# Rev_A.net
KiCad netlist of a schematic drawn in EAGLE
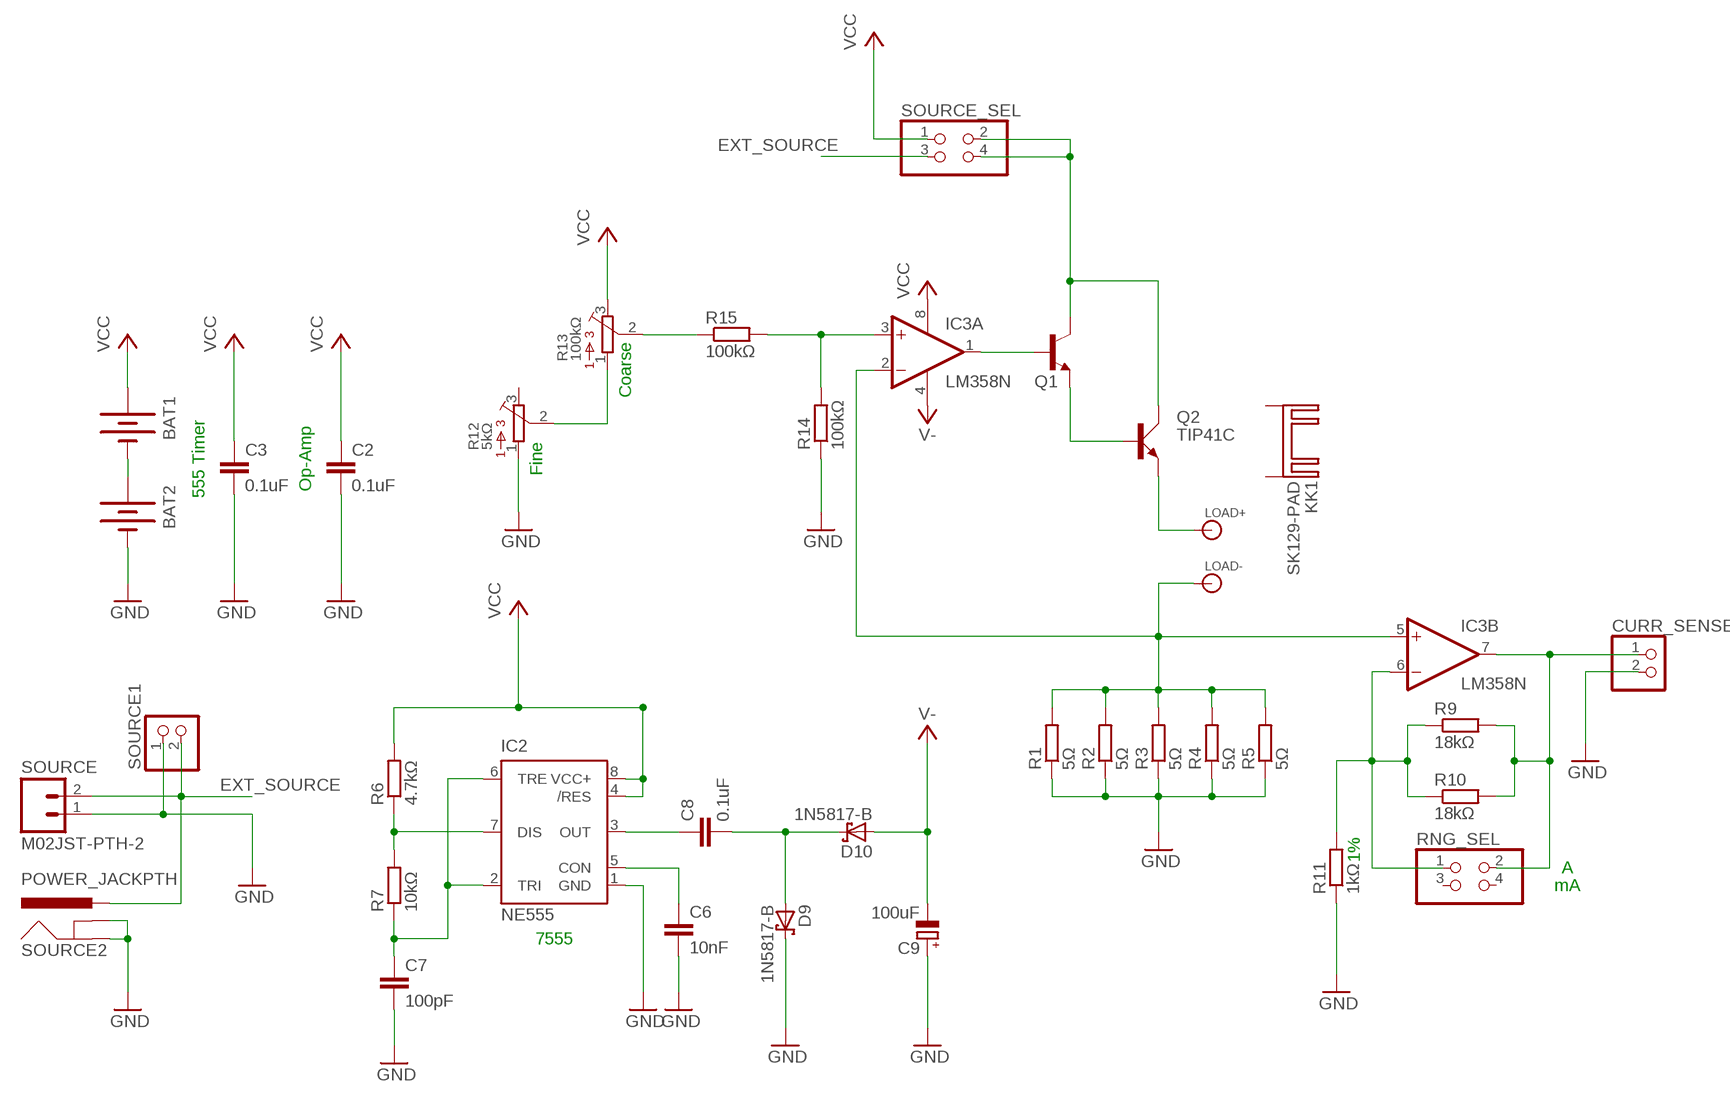
[diagram p0: schematic, sheet 1]

(export (version "E")
  (design (tool "Eeschema 10.0.6"))
  (components
    (comp (ref "BAT1")
      (value "BATTERYAA")
      (footprint "eagle-import:BATTERY-AA")
      (libsource (lib "eagle-import") (part "BATTERYAA"))
    )
    (comp (ref "BAT2")
      (value "BATTERYAA")
      (footprint "eagle-import:BATTERY-AA")
      (libsource (lib "eagle-import") (part "BATTERYAA"))
    )
    (comp (ref "C2")
      (value "0.1uF")
      (footprint "eagle-import:C050-025X075")
      (libsource (lib "eagle-import") (part "C-EU050-025X075"))
    )
    (comp (ref "C3")
      (value "0.1uF")
      (footprint "eagle-import:C050-025X075")
      (libsource (lib "eagle-import") (part "C-EU050-025X075"))
    )
    (comp (ref "C6")
      (value "10nF")
      (footprint "eagle-import:C050-025X075")
      (libsource (lib "eagle-import") (part "C-EU050-025X075"))
    )
    (comp (ref "C7")
      (value "100pF")
      (footprint "eagle-import:C025-025X050")
      (libsource (lib "eagle-import") (part "C-EU025-025X050"))
    )
    (comp (ref "C8")
      (value "0.1uF")
      (footprint "eagle-import:C050-025X075")
      (libsource (lib "eagle-import") (part "C-EU050-025X075"))
    )
    (comp (ref "C9")
      (value "100uF")
      (footprint "eagle-import:E2,5-6")
      (libsource (lib "eagle-import") (part "CPOL-EUE2.5-6"))
    )
    (comp (ref "CURR_SENSE")
      (value "PINHD-1X2")
      (footprint "eagle-import:1X02")
      (libsource (lib "eagle-import") (part "PINHD-1X2"))
    )
    (comp (ref "D9")
      (value "1N5817-B")
      (footprint "eagle-import:DO41-7.6")
      (libsource (lib "eagle-import") (part "1N5817-B"))
    )
    (comp (ref "D10")
      (value "1N5817-B")
      (footprint "eagle-import:DO41-7.6")
      (libsource (lib "eagle-import") (part "1N5817-B"))
    )
    (comp (ref "IC2")
      (value "NE555")
      (footprint "eagle-import:DIL-08")
      (fields (field (name "MF") "Arrow Electronics") (field (name "MPN") "NE555N"))
      (libsource (lib "eagle-import") (part "NE555"))
    )
    (comp (ref "IC3")
      (value "LM358N")
      (footprint "eagle-import:DIL08")
      (libsource (lib "eagle-import") (part "LM358N"))
    )
    (comp (ref "KK1")
      (value "SK129-PAD")
      (footprint "eagle-import:SK129")
      (libsource (lib "eagle-import") (part "SK129-PAD"))
    )
    (comp (ref "LOAD+")
      (value "BANANA_CONN")
      (footprint "eagle-import:BANANA_CONN")
      (libsource (lib "eagle-import") (part "BANANA_CONN"))
    )
    (comp (ref "LOAD-")
      (value "BANANA_CONN")
      (footprint "eagle-import:BANANA_CONN")
      (libsource (lib "eagle-import") (part "BANANA_CONN"))
    )
    (comp (ref "Q1")
      (value "2N5551-NPN-TO92-CBE")
      (footprint "eagle-import:TO92-CBE")
      (libsource (lib "eagle-import") (part "-NPN-TO92-CBE2N5551"))
    )
    (comp (ref "Q2")
      (value "TIP41C")
      (footprint "eagle-import:TO220AV")
      (libsource (lib "eagle-import") (part "TIP41C"))
    )
    (comp (ref "R1")
      (value "5Ω")
      (footprint "eagle-import:P0613_15")
      (libsource (lib "eagle-import") (part "R-EU_0613/15"))
    )
    (comp (ref "R2")
      (value "5Ω")
      (footprint "eagle-import:P0613_15")
      (libsource (lib "eagle-import") (part "R-EU_0613/15"))
    )
    (comp (ref "R3")
      (value "5Ω")
      (footprint "eagle-import:P0613_15")
      (libsource (lib "eagle-import") (part "R-EU_0613/15"))
    )
    (comp (ref "R4")
      (value "5Ω")
      (footprint "eagle-import:P0613_15")
      (libsource (lib "eagle-import") (part "R-EU_0613/15"))
    )
    (comp (ref "R5")
      (value "5Ω")
      (footprint "eagle-import:P0613_15")
      (libsource (lib "eagle-import") (part "R-EU_0613/15"))
    )
    (comp (ref "R6")
      (value "4.7kΩ")
      (footprint "eagle-import:0207_10")
      (libsource (lib "eagle-import") (part "resistor_R-EU_0207/10"))
    )
    (comp (ref "R7")
      (value "10kΩ")
      (footprint "eagle-import:0207_10")
      (libsource (lib "eagle-import") (part "resistor_R-EU_0207/10"))
    )
    (comp (ref "R9")
      (value "18kΩ")
      (footprint "eagle-import:0207_10")
      (libsource (lib "eagle-import") (part "resistor_R-EU_0207/10"))
    )
    (comp (ref "R10")
      (value "18kΩ")
      (footprint "eagle-import:0207_10")
      (libsource (lib "eagle-import") (part "resistor_R-EU_0207/10"))
    )
    (comp (ref "R11")
      (value "1kΩ")
      (footprint "eagle-import:0207_10")
      (libsource (lib "eagle-import") (part "resistor_R-EU_0207/10"))
    )
    (comp (ref "R12")
      (value "5kΩ")
      (footprint "eagle-import:3362U")
      (libsource (lib "eagle-import") (part "3362U"))
    )
    (comp (ref "R13")
      (value "100kΩ")
      (footprint "eagle-import:3362U")
      (libsource (lib "eagle-import") (part "3362U"))
    )
    (comp (ref "R14")
      (value "100kΩ")
      (footprint "eagle-import:0207_10")
      (libsource (lib "eagle-import") (part "resistor_R-EU_0207/10"))
    )
    (comp (ref "R15")
      (value "100kΩ")
      (footprint "eagle-import:0207_10")
      (libsource (lib "eagle-import") (part "resistor_R-EU_0207/10"))
    )
    (comp (ref "RNG_SEL")
      (value "PINHD-2X2")
      (footprint "eagle-import:2X02")
      (libsource (lib "eagle-import") (part "PINHD-2X2"))
    )
    (comp (ref "SOURCE")
      (value "M02JST-PTH-2")
      (footprint "eagle-import:JST-2-PTH")
      (libsource (lib "eagle-import") (part "M02JST-PTH-2"))
    )
    (comp (ref "SOURCE1")
      (value "PINHD-1X2")
      (footprint "eagle-import:1X02")
      (libsource (lib "eagle-import") (part "PINHD-1X2"))
    )
    (comp (ref "SOURCE2")
      (value "POWER_JACKPTH")
      (footprint "eagle-import:POWER_JACK_PTH")
      (libsource (lib "eagle-import") (part "POWER_JACKPTH"))
    )
    (comp (ref "SOURCE_SEL")
      (value "PINHD-2X2")
      (footprint "eagle-import:2X02")
      (libsource (lib "eagle-import") (part "PINHD-2X2"))
    )
  )
  (nets
    (net (code "1") (name "/EXT_SOURCE") (class "Default")
      (node (ref "SOURCE") (pin "2") (pinfunction "2_2") (pintype "passive"))
      (node (ref "SOURCE1") (pin "2") (pinfunction "2_2") (pintype "passive"))
      (node (ref "SOURCE2") (pin "PWR") (pinfunction "PWR_PWR") (pintype "bidirectional"))
      (node (ref "SOURCE_SEL") (pin "3") (pinfunction "3_3") (pintype "passive"))
    )
    (net (code "2") (name "GND") (class "Default")
      (node (ref "BAT2") (pin "GND@1") (pinfunction "-_GND@1") (pintype "power_in"))
      (node (ref "C2") (pin "2") (pinfunction "2_2") (pintype "passive"))
      (node (ref "C3") (pin "2") (pinfunction "2_2") (pintype "passive"))
      (node (ref "C6") (pin "2") (pinfunction "2_2") (pintype "passive"))
      (node (ref "C7") (pin "2") (pinfunction "2_2") (pintype "passive"))
      (node (ref "C9") (pin "+") (pinfunction "+_+") (pintype "passive"))
      (node (ref "CURR_SENSE") (pin "2") (pinfunction "2_2") (pintype "passive"))
      (node (ref "D9") (pin "C") (pinfunction "C_C") (pintype "passive"))
      (node (ref "IC2") (pin "1") (pinfunction "GND_1") (pintype "power_in"))
      (node (ref "R1") (pin "1") (pinfunction "1_1") (pintype "passive"))
      (node (ref "R11") (pin "1") (pinfunction "1_1") (pintype "passive"))
      (node (ref "R12") (pin "1") (pinfunction "1_1") (pintype "passive"))
      (node (ref "R14") (pin "1") (pinfunction "1_1") (pintype "passive"))
      (node (ref "R2") (pin "1") (pinfunction "1_1") (pintype "passive"))
      (node (ref "R3") (pin "1") (pinfunction "1_1") (pintype "passive"))
      (node (ref "R4") (pin "1") (pinfunction "1_1") (pintype "passive"))
      (node (ref "R5") (pin "1") (pinfunction "1_1") (pintype "passive"))
      (node (ref "SOURCE") (pin "1") (pinfunction "1_1") (pintype "passive"))
      (node (ref "SOURCE1") (pin "1") (pinfunction "1_1") (pintype "passive"))
      (node (ref "SOURCE2") (pin "GND") (pinfunction "GND_GND") (pintype "bidirectional"))
      (node (ref "SOURCE2") (pin "GNDBREAK") (pinfunction "GNDBREAK_GNDBREAK") (pintype "bidirectional"))
    )
    (net (code "3") (name "Net-(BAT1--)") (class "Default")
      (node (ref "BAT1") (pin "GND@1") (pinfunction "-_GND@1") (pintype "power_in"))
      (node (ref "BAT2") (pin "PWR@1") (pinfunction "+_PWR@1") (pintype "power_in"))
    )
    (net (code "4") (name "Net-(C8-Pad2)") (class "Default")
      (node (ref "C8") (pin "2") (pinfunction "2_2") (pintype "passive"))
      (node (ref "D10") (pin "C") (pinfunction "C_C") (pintype "passive"))
      (node (ref "D9") (pin "A") (pinfunction "A_A") (pintype "passive"))
    )
    (net (code "5") (name "Net-(IC2-CON)") (class "Default")
      (node (ref "C6") (pin "1") (pinfunction "1_1") (pintype "passive"))
      (node (ref "IC2") (pin "5") (pinfunction "CON_5") (pintype "input"))
    )
    (net (code "6") (name "Net-(IC2-DIS)") (class "Default")
      (node (ref "IC2") (pin "7") (pinfunction "DIS_7") (pintype "input"))
      (node (ref "R6") (pin "1") (pinfunction "1_1") (pintype "passive"))
      (node (ref "R7") (pin "2") (pinfunction "2_2") (pintype "passive"))
    )
    (net (code "7") (name "Net-(IC2-OUT)") (class "Default")
      (node (ref "C8") (pin "1") (pinfunction "1_1") (pintype "passive"))
      (node (ref "IC2") (pin "3") (pinfunction "OUT_3") (pintype "output"))
    )
    (net (code "8") (name "Net-(IC2-TRE)") (class "Default")
      (node (ref "C7") (pin "1") (pinfunction "1_1") (pintype "passive"))
      (node (ref "IC2") (pin "2") (pinfunction "TRI_2") (pintype "input"))
      (node (ref "IC2") (pin "6") (pinfunction "TRE_6") (pintype "input"))
      (node (ref "R7") (pin "1") (pinfunction "1_1") (pintype "passive"))
    )
    (net (code "9") (name "Net-(IC3A-+IN)") (class "Default")
      (node (ref "IC3") (pin "3") (pinfunction "+IN_3") (pintype "input"))
      (node (ref "R14") (pin "2") (pinfunction "2_2") (pintype "passive"))
      (node (ref "R15") (pin "2") (pinfunction "2_2") (pintype "passive"))
    )
    (net (code "10") (name "Net-(IC3A--IN)") (class "Default")
      (node (ref "IC3") (pin "2") (pinfunction "-IN_2") (pintype "input"))
      (node (ref "IC3") (pin "5") (pinfunction "+IN_5") (pintype "input"))
      (node (ref "LOAD-") (pin "P$1") (pinfunction "1_P$1") (pintype "passive"))
      (node (ref "R1") (pin "2") (pinfunction "2_2") (pintype "passive"))
      (node (ref "R2") (pin "2") (pinfunction "2_2") (pintype "passive"))
      (node (ref "R3") (pin "2") (pinfunction "2_2") (pintype "passive"))
      (node (ref "R4") (pin "2") (pinfunction "2_2") (pintype "passive"))
      (node (ref "R5") (pin "2") (pinfunction "2_2") (pintype "passive"))
    )
    (net (code "11") (name "Net-(IC3A-OUT)") (class "Default")
      (node (ref "IC3") (pin "1") (pinfunction "OUT_1") (pintype "output"))
      (node (ref "Q1") (pin "B") (pinfunction "B_B") (pintype "passive"))
    )
    (net (code "12") (name "Net-(IC3B--IN)") (class "Default")
      (node (ref "IC3") (pin "6") (pinfunction "-IN_6") (pintype "input"))
      (node (ref "R10") (pin "1") (pinfunction "1_1") (pintype "passive"))
      (node (ref "R11") (pin "2") (pinfunction "2_2") (pintype "passive"))
      (node (ref "R9") (pin "1") (pinfunction "1_1") (pintype "passive"))
      (node (ref "RNG_SEL") (pin "1") (pinfunction "1_1") (pintype "passive"))
    )
    (net (code "13") (name "Net-(IC3B-OUT)") (class "Default")
      (node (ref "CURR_SENSE") (pin "1") (pinfunction "1_1") (pintype "passive"))
      (node (ref "IC3") (pin "7") (pinfunction "OUT_7") (pintype "output"))
      (node (ref "R10") (pin "2") (pinfunction "2_2") (pintype "passive"))
      (node (ref "R9") (pin "2") (pinfunction "2_2") (pintype "passive"))
      (node (ref "RNG_SEL") (pin "2") (pinfunction "2_2") (pintype "passive"))
    )
    (net (code "14") (name "Net-(LOAD+-1)") (class "Default")
      (node (ref "LOAD+") (pin "P$1") (pinfunction "1_P$1") (pintype "passive"))
      (node (ref "Q2") (pin "E") (pinfunction "E_E") (pintype "passive"))
    )
    (net (code "15") (name "Net-(Q1-PadC)") (class "Default")
      (node (ref "Q1") (pin "C") (pinfunction "C_C") (pintype "passive"))
      (node (ref "Q2") (pin "C") (pinfunction "C_C") (pintype "passive"))
      (node (ref "SOURCE_SEL") (pin "2") (pinfunction "2_2") (pintype "passive"))
      (node (ref "SOURCE_SEL") (pin "4") (pinfunction "4_4") (pintype "passive"))
    )
    (net (code "16") (name "Net-(Q1-PadE)") (class "Default")
      (node (ref "Q1") (pin "E") (pinfunction "E_E") (pintype "passive"))
      (node (ref "Q2") (pin "B") (pinfunction "B_B") (pintype "passive"))
    )
    (net (code "17") (name "Net-(R12-Pad2)") (class "Default")
      (node (ref "R12") (pin "2") (pinfunction "2_2") (pintype "passive"))
      (node (ref "R13") (pin "1") (pinfunction "1_1") (pintype "passive"))
    )
    (net (code "18") (name "Net-(R13-Pad2)") (class "Default")
      (node (ref "R13") (pin "2") (pinfunction "2_2") (pintype "passive"))
      (node (ref "R15") (pin "1") (pinfunction "1_1") (pintype "passive"))
    )
    (net (code "19") (name "V-") (class "Default")
      (node (ref "C9") (pin "-") (pinfunction "-_-") (pintype "passive"))
      (node (ref "D10") (pin "A") (pinfunction "A_A") (pintype "passive"))
      (node (ref "IC3") (pin "4") (pinfunction "V-_4") (pintype "power_in"))
    )
    (net (code "20") (name "VCC") (class "Default")
      (node (ref "BAT1") (pin "PWR@1") (pinfunction "+_PWR@1") (pintype "power_in"))
      (node (ref "C2") (pin "1") (pinfunction "1_1") (pintype "passive"))
      (node (ref "C3") (pin "1") (pinfunction "1_1") (pintype "passive"))
      (node (ref "IC2") (pin "4") (pinfunction "/RES_4") (pintype "input"))
      (node (ref "IC2") (pin "8") (pinfunction "VCC+_8") (pintype "power_in"))
      (node (ref "IC3") (pin "8") (pinfunction "V+_8") (pintype "power_in"))
      (node (ref "R13") (pin "3") (pinfunction "3_3") (pintype "passive"))
      (node (ref "R6") (pin "2") (pinfunction "2_2") (pintype "passive"))
      (node (ref "SOURCE_SEL") (pin "1") (pinfunction "1_1") (pintype "passive"))
    )
    (net (code "21") (name "unconnected-(KK1-K-PadA2,5)") (class "Default")
      (node (ref "KK1") (pin "A2,5") (pinfunction "K_A2,5") (pintype "passive"))
    )
    (net (code "22") (name "unconnected-(KK1-K-PadB2,5)") (class "Default")
      (node (ref "KK1") (pin "B2,5") (pinfunction "K_B2,5") (pintype "passive"))
    )
    (net (code "23") (name "unconnected-(R12-Pad3)") (class "Default")
      (node (ref "R12") (pin "3") (pinfunction "3_3") (pintype "passive"))
    )
    (net (code "24") (name "unconnected-(RNG_SEL-Pad3)") (class "Default")
      (node (ref "RNG_SEL") (pin "3") (pinfunction "3_3") (pintype "passive"))
    )
    (net (code "25") (name "unconnected-(RNG_SEL-Pad4)") (class "Default")
      (node (ref "RNG_SEL") (pin "4") (pinfunction "4_4") (pintype "passive"))
    )
  )
)
